# C52.net
KiCad netlist of a schematic drawn in Altium Designer
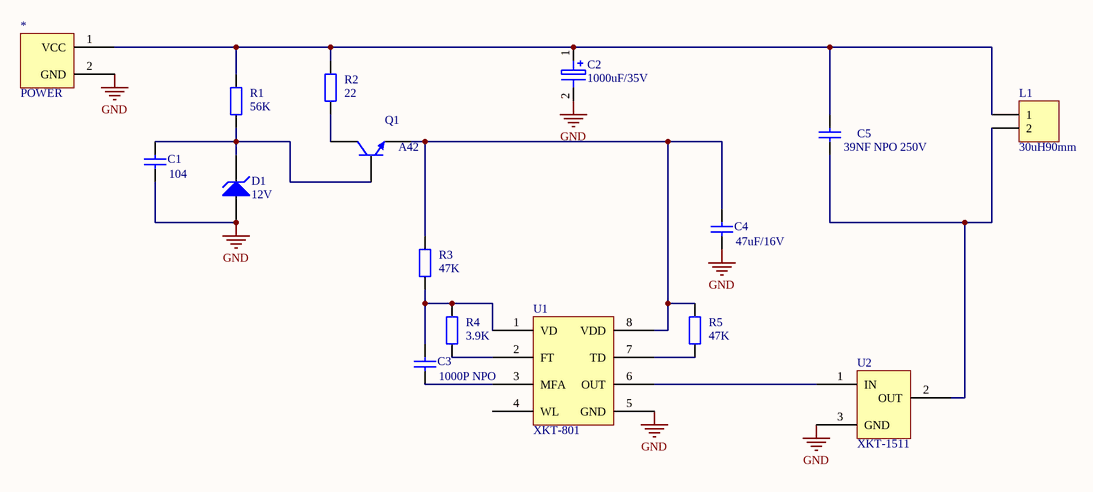
[diagram p0: C52.SchDoc]

(export (version "E")
  (design (tool "Eeschema 10.0.6"))
  (components
    (comp (ref "*")
      (value "POWER")
      (footprint "POWER")
      (libsource (lib "Integrated_Library_3") (part "POWER"))
    )
    (comp (ref "C1")
      (value "104")
      (footprint "RAD-0.3")
      (description "Capacitor")
      (fields (field (name "Comment") "Cap") (field (name "PUBLISHER") "Altium Limited"))
      (libsource (lib "Miscellaneous Devices") (part "Cap"))
    )
    (comp (ref "C2")
      (value "1000uF/35V")
      (footprint "C2")
      (libsource (lib "Integrated_Library_3") (part "C2"))
    )
    (comp (ref "C3")
      (value "1000P NPO")
      (footprint "RAD-0.3")
      (description "Capacitor")
      (fields (field (name "Comment") "Cap") (field (name "PUBLISHER") "Altium Limited"))
      (libsource (lib "Miscellaneous Devices") (part "Cap"))
    )
    (comp (ref "C4")
      (value "47uF/16V")
      (footprint "RAD-0.3")
      (description "Capacitor")
      (fields (field (name "Comment") "Cap") (field (name "PUBLISHER") "Altium Limited"))
      (libsource (lib "Miscellaneous Devices") (part "Cap"))
    )
    (comp (ref "C5")
      (value "39NF NPO 250V")
      (footprint "RAD-0.3")
      (description "Capacitor")
      (fields (field (name "Comment") "Cap") (field (name "PUBLISHER") "Altium Limited"))
      (libsource (lib "Miscellaneous Devices") (part "Cap"))
    )
    (comp (ref "D1")
      (value "12V")
      (footprint "DIODE-0.7")
      (description "Zener Diode")
      (fields (field (name "PUBLISHER") "Altium Limited"))
      (libsource (lib "Miscellaneous Devices") (part "D Zener"))
    )
    (comp (ref "L1")
      (value "30uH90mm")
      (footprint "HDR1X2")
      (description "Header, 2-Pin")
      (fields (field (name "PUBLISHER") "Altium Limited"))
      (libsource (lib "Miscellaneous Connectors") (part "Header 2"))
    )
    (comp (ref "Q1")
      (value "A42")
      (footprint "TO-226-AA")
      (description "NPN Bipolar Transistor")
      (fields (field (name "PUBLISHER") "Altium Limited"))
      (libsource (lib "Miscellaneous Devices") (part "NPN"))
    )
    (comp (ref "R1")
      (value "56K")
      (footprint "AXIAL-0.4")
      (description "Resistor")
      (fields (field (name "Comment") "Res2") (field (name "PUBLISHER") "Altium Limited"))
      (libsource (lib "Miscellaneous Devices") (part "Res2"))
    )
    (comp (ref "R2")
      (value "22")
      (footprint "AXIAL-0.4")
      (description "Resistor")
      (fields (field (name "Comment") "Res2") (field (name "PUBLISHER") "Altium Limited"))
      (libsource (lib "Miscellaneous Devices") (part "Res2"))
    )
    (comp (ref "R3")
      (value "47K")
      (footprint "AXIAL-0.4")
      (description "Resistor")
      (fields (field (name "Comment") "Res2") (field (name "PUBLISHER") "Altium Limited"))
      (libsource (lib "Miscellaneous Devices") (part "Res2"))
    )
    (comp (ref "R4")
      (value "3.9K")
      (footprint "AXIAL-0.4")
      (description "Resistor")
      (fields (field (name "Comment") "Res2") (field (name "PUBLISHER") "Altium Limited"))
      (libsource (lib "Miscellaneous Devices") (part "Res2"))
    )
    (comp (ref "R5")
      (value "47K")
      (footprint "AXIAL-0.4")
      (description "Resistor")
      (fields (field (name "Comment") "Res2") (field (name "PUBLISHER") "Altium Limited"))
      (libsource (lib "Miscellaneous Devices") (part "Res2"))
    )
    (comp (ref "U1")
      (value "XKT-801")
      (footprint "XKT-801 - duplicate1")
      (libsource (lib "Integrated_Library_3") (part "XKT-801"))
    )
    (comp (ref "U2")
      (value "XKT-1511")
      (footprint "XKT-1511")
      (libsource (lib "Integrated_Library_3") (part "XKT-1511"))
    )
  )
  (nets
    (net (code "1") (name "GND") (class "Default")
      (node (ref "*") (pin "2") (pinfunction "GND_2") (pintype "passive"))
      (node (ref "C1") (pin "1") (pinfunction "1_1") (pintype "passive"))
      (node (ref "C2") (pin "2") (pinfunction "E_2") (pintype "passive"))
      (node (ref "C4") (pin "1") (pinfunction "1_1") (pintype "passive"))
      (node (ref "D1") (pin "1") (pinfunction "A_1") (pintype "passive"))
      (node (ref "U1") (pin "5") (pinfunction "GND_5") (pintype "passive"))
      (node (ref "U2") (pin "3") (pinfunction "GND_3") (pintype "passive"))
    )
    (net (code "2") (name "Net-(*-VCC)") (class "Default")
      (node (ref "*") (pin "1") (pinfunction "VCC_1") (pintype "passive"))
      (node (ref "C2") (pin "1") (pinfunction "1_1") (pintype "passive"))
      (node (ref "C5") (pin "2") (pinfunction "2_2") (pintype "passive"))
      (node (ref "L1") (pin "1") (pinfunction "1_1") (pintype "passive"))
      (node (ref "R1") (pin "2") (pinfunction "2_2") (pintype "passive"))
      (node (ref "R2") (pin "2") (pinfunction "2_2") (pintype "passive"))
    )
    (net (code "3") (name "Net-(D1-K)") (class "Default")
      (node (ref "C1") (pin "2") (pinfunction "2_2") (pintype "passive"))
      (node (ref "D1") (pin "2") (pinfunction "K_2") (pintype "passive"))
      (node (ref "Q1") (pin "2") (pinfunction "B_2") (pintype "passive"))
      (node (ref "R1") (pin "1") (pinfunction "1_1") (pintype "passive"))
    )
    (net (code "4") (name "Net-(Q1-C)") (class "Default")
      (node (ref "Q1") (pin "1") (pinfunction "C_1") (pintype "passive"))
      (node (ref "R2") (pin "1") (pinfunction "1_1") (pintype "passive"))
    )
    (net (code "5") (name "Net-(Q1-E)") (class "Default")
      (node (ref "C4") (pin "2") (pinfunction "2_2") (pintype "passive"))
      (node (ref "Q1") (pin "3") (pinfunction "E_3") (pintype "passive"))
      (node (ref "R3") (pin "2") (pinfunction "2_2") (pintype "passive"))
      (node (ref "R5") (pin "2") (pinfunction "2_2") (pintype "passive"))
      (node (ref "U1") (pin "8") (pinfunction "VDD_8") (pintype "passive"))
    )
    (net (code "6") (name "Net-(U1-FT)") (class "Default")
      (node (ref "R4") (pin "1") (pinfunction "1_1") (pintype "passive"))
      (node (ref "U1") (pin "2") (pinfunction "FT_2") (pintype "passive"))
    )
    (net (code "7") (name "Net-(U1-MFA)") (class "Default")
      (node (ref "C3") (pin "1") (pinfunction "1_1") (pintype "passive"))
      (node (ref "U1") (pin "3") (pinfunction "MFA_3") (pintype "passive"))
    )
    (net (code "8") (name "Net-(U1-OUT)") (class "Default")
      (node (ref "U1") (pin "6") (pinfunction "OUT_6") (pintype "passive"))
      (node (ref "U2") (pin "1") (pinfunction "IN_1") (pintype "passive"))
    )
    (net (code "9") (name "Net-(U1-TD)") (class "Default")
      (node (ref "R5") (pin "1") (pinfunction "1_1") (pintype "passive"))
      (node (ref "U1") (pin "7") (pinfunction "TD_7") (pintype "passive"))
    )
    (net (code "10") (name "Net-(U1-VD)") (class "Default")
      (node (ref "C3") (pin "2") (pinfunction "2_2") (pintype "passive"))
      (node (ref "R3") (pin "1") (pinfunction "1_1") (pintype "passive"))
      (node (ref "R4") (pin "2") (pinfunction "2_2") (pintype "passive"))
      (node (ref "U1") (pin "1") (pinfunction "VD_1") (pintype "passive"))
    )
    (net (code "11") (name "Net-(U2-OUT)") (class "Default")
      (node (ref "C5") (pin "1") (pinfunction "1_1") (pintype "passive"))
      (node (ref "L1") (pin "2") (pinfunction "2_2") (pintype "passive"))
      (node (ref "U2") (pin "2") (pinfunction "OUT_2") (pintype "passive"))
    )
    (net (code "12") (name "unconnected-(U1-WL-Pad4)") (class "Default")
      (node (ref "U1") (pin "4") (pinfunction "WL_4") (pintype "passive"))
    )
  )
)
